# power_distribution_pcb.net
KiCad netlist of a schematic drawn in EAGLE
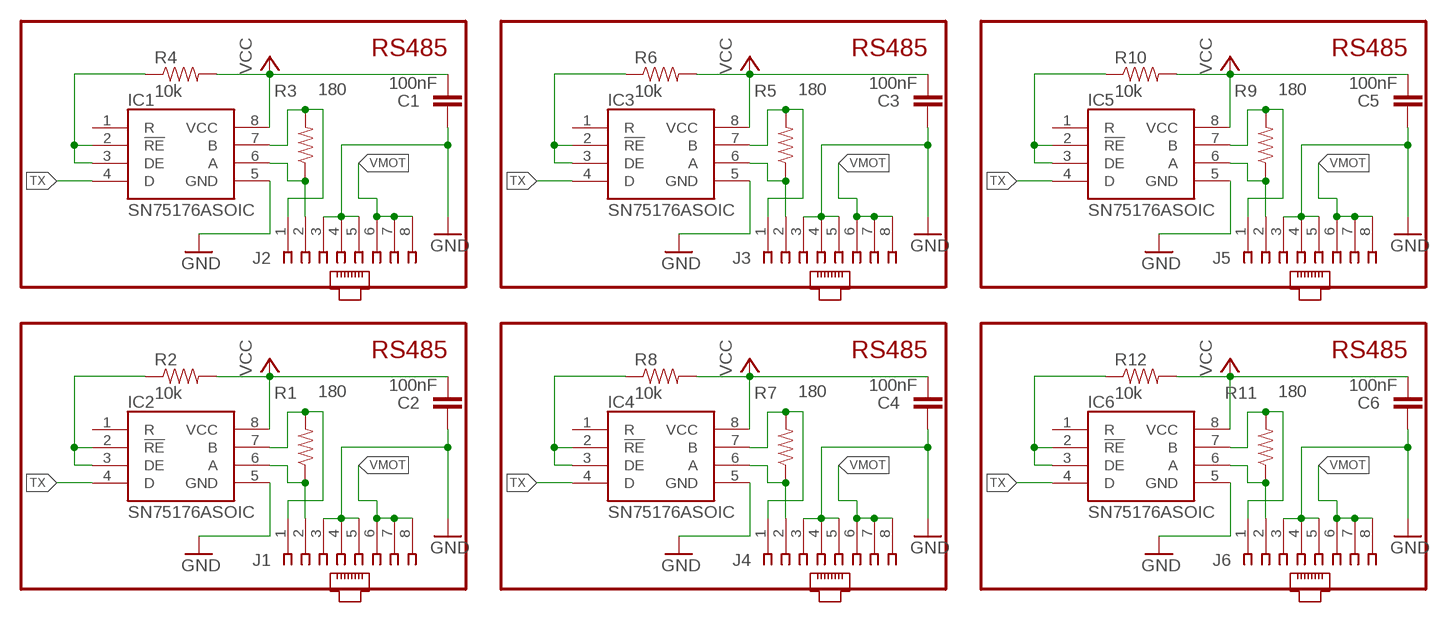
[diagram p0: schematic, sheet 1]

(export (version "E")
  (design (tool "Eeschema 10.0.6"))
  (components
    (comp (ref "C1")
      (value "100nF")
      (footprint "eagle-import:0805")
      (libsource (lib "eagle-import") (part "CAP0805"))
    )
    (comp (ref "C2")
      (value "100nF")
      (footprint "eagle-import:0805")
      (libsource (lib "eagle-import") (part "CAP0805"))
    )
    (comp (ref "C3")
      (value "100nF")
      (footprint "eagle-import:0805")
      (libsource (lib "eagle-import") (part "CAP0805"))
    )
    (comp (ref "C4")
      (value "100nF")
      (footprint "eagle-import:0805")
      (libsource (lib "eagle-import") (part "CAP0805"))
    )
    (comp (ref "C5")
      (value "100nF")
      (footprint "eagle-import:0805")
      (libsource (lib "eagle-import") (part "CAP0805"))
    )
    (comp (ref "C6")
      (value "100nF")
      (footprint "eagle-import:0805")
      (libsource (lib "eagle-import") (part "CAP0805"))
    )
    (comp (ref "IC1")
      (value "SN75176ASOIC")
      (footprint "eagle-import:SO08")
      (libsource (lib "eagle-import") (part "SN75176ASOIC"))
    )
    (comp (ref "IC2")
      (value "SN75176ASOIC")
      (footprint "eagle-import:SO08")
      (libsource (lib "eagle-import") (part "SN75176ASOIC"))
    )
    (comp (ref "IC3")
      (value "SN75176ASOIC")
      (footprint "eagle-import:SO08")
      (libsource (lib "eagle-import") (part "SN75176ASOIC"))
    )
    (comp (ref "IC4")
      (value "SN75176ASOIC")
      (footprint "eagle-import:SO08")
      (libsource (lib "eagle-import") (part "SN75176ASOIC"))
    )
    (comp (ref "IC5")
      (value "SN75176ASOIC")
      (footprint "eagle-import:SO08")
      (libsource (lib "eagle-import") (part "SN75176ASOIC"))
    )
    (comp (ref "IC6")
      (value "SN75176ASOIC")
      (footprint "eagle-import:SO08")
      (libsource (lib "eagle-import") (part "SN75176ASOIC"))
    )
    (comp (ref "J1")
      (value "520426-4")
      (footprint "eagle-import:520426-4")
      (libsource (lib "eagle-import") (part "520426-4"))
    )
    (comp (ref "J2")
      (value "520426-4")
      (footprint "eagle-import:520426-4")
      (libsource (lib "eagle-import") (part "520426-4"))
    )
    (comp (ref "J3")
      (value "520426-4")
      (footprint "eagle-import:520426-4")
      (libsource (lib "eagle-import") (part "520426-4"))
    )
    (comp (ref "J4")
      (value "520426-4")
      (footprint "eagle-import:520426-4")
      (libsource (lib "eagle-import") (part "520426-4"))
    )
    (comp (ref "J5")
      (value "520426-4")
      (footprint "eagle-import:520426-4")
      (libsource (lib "eagle-import") (part "520426-4"))
    )
    (comp (ref "J6")
      (value "520426-4")
      (footprint "eagle-import:520426-4")
      (libsource (lib "eagle-import") (part "520426-4"))
    )
    (comp (ref "R1")
      (value "180")
      (footprint "eagle-import:0805")
      (libsource (lib "eagle-import") (part "RESISTOR"))
    )
    (comp (ref "R2")
      (value "10k")
      (footprint "eagle-import:0805")
      (libsource (lib "eagle-import") (part "RESISTOR"))
    )
    (comp (ref "R3")
      (value "180")
      (footprint "eagle-import:0805")
      (libsource (lib "eagle-import") (part "RESISTOR"))
    )
    (comp (ref "R4")
      (value "10k")
      (footprint "eagle-import:0805")
      (libsource (lib "eagle-import") (part "RESISTOR"))
    )
    (comp (ref "R5")
      (value "180")
      (footprint "eagle-import:0805")
      (libsource (lib "eagle-import") (part "RESISTOR"))
    )
    (comp (ref "R6")
      (value "10k")
      (footprint "eagle-import:0805")
      (libsource (lib "eagle-import") (part "RESISTOR"))
    )
    (comp (ref "R7")
      (value "180")
      (footprint "eagle-import:0805")
      (libsource (lib "eagle-import") (part "RESISTOR"))
    )
    (comp (ref "R8")
      (value "10k")
      (footprint "eagle-import:0805")
      (libsource (lib "eagle-import") (part "RESISTOR"))
    )
    (comp (ref "R9")
      (value "180")
      (footprint "eagle-import:0805")
      (libsource (lib "eagle-import") (part "RESISTOR"))
    )
    (comp (ref "R10")
      (value "10k")
      (footprint "eagle-import:0805")
      (libsource (lib "eagle-import") (part "RESISTOR"))
    )
    (comp (ref "R11")
      (value "180")
      (footprint "eagle-import:0805")
      (libsource (lib "eagle-import") (part "RESISTOR"))
    )
    (comp (ref "R12")
      (value "10k")
      (footprint "eagle-import:0805")
      (libsource (lib "eagle-import") (part "RESISTOR"))
    )
  )
  (nets
    (net (code "1") (name "GND") (class "Default")
      (node (ref "C1") (pin "1") (pinfunction "1_1") (pintype "passive"))
      (node (ref "C2") (pin "1") (pinfunction "1_1") (pintype "passive"))
      (node (ref "C3") (pin "1") (pinfunction "1_1") (pintype "passive"))
      (node (ref "C4") (pin "1") (pinfunction "1_1") (pintype "passive"))
      (node (ref "C5") (pin "1") (pinfunction "1_1") (pintype "passive"))
      (node (ref "C6") (pin "1") (pinfunction "1_1") (pintype "passive"))
      (node (ref "IC1") (pin "5") (pinfunction "GND_5") (pintype "bidirectional"))
      (node (ref "IC2") (pin "5") (pinfunction "GND_5") (pintype "bidirectional"))
      (node (ref "IC3") (pin "5") (pinfunction "GND_5") (pintype "bidirectional"))
      (node (ref "IC4") (pin "5") (pinfunction "GND_5") (pintype "bidirectional"))
      (node (ref "IC5") (pin "5") (pinfunction "GND_5") (pintype "bidirectional"))
      (node (ref "IC6") (pin "5") (pinfunction "GND_5") (pintype "bidirectional"))
      (node (ref "J1") (pin "3") (pinfunction "3_3") (pintype "passive"))
      (node (ref "J1") (pin "4") (pinfunction "4_4") (pintype "passive"))
      (node (ref "J1") (pin "5") (pinfunction "5_5") (pintype "passive"))
      (node (ref "J2") (pin "3") (pinfunction "3_3") (pintype "passive"))
      (node (ref "J2") (pin "4") (pinfunction "4_4") (pintype "passive"))
      (node (ref "J2") (pin "5") (pinfunction "5_5") (pintype "passive"))
      (node (ref "J3") (pin "3") (pinfunction "3_3") (pintype "passive"))
      (node (ref "J3") (pin "4") (pinfunction "4_4") (pintype "passive"))
      (node (ref "J3") (pin "5") (pinfunction "5_5") (pintype "passive"))
      (node (ref "J4") (pin "3") (pinfunction "3_3") (pintype "passive"))
      (node (ref "J4") (pin "4") (pinfunction "4_4") (pintype "passive"))
      (node (ref "J4") (pin "5") (pinfunction "5_5") (pintype "passive"))
      (node (ref "J5") (pin "3") (pinfunction "3_3") (pintype "passive"))
      (node (ref "J5") (pin "4") (pinfunction "4_4") (pintype "passive"))
      (node (ref "J5") (pin "5") (pinfunction "5_5") (pintype "passive"))
      (node (ref "J6") (pin "3") (pinfunction "3_3") (pintype "passive"))
      (node (ref "J6") (pin "4") (pinfunction "4_4") (pintype "passive"))
      (node (ref "J6") (pin "5") (pinfunction "5_5") (pintype "passive"))
    )
    (net (code "2") (name "Net-(IC1-A)") (class "Default")
      (node (ref "IC1") (pin "6") (pinfunction "A_6") (pintype "bidirectional"))
      (node (ref "J2") (pin "2") (pinfunction "2_2") (pintype "passive"))
      (node (ref "R3") (pin "1") (pinfunction "1_1") (pintype "passive"))
    )
    (net (code "3") (name "Net-(IC1-B)") (class "Default")
      (node (ref "IC1") (pin "7") (pinfunction "B_7") (pintype "bidirectional"))
      (node (ref "J2") (pin "1") (pinfunction "1_1") (pintype "passive"))
      (node (ref "R3") (pin "2") (pinfunction "2_2") (pintype "passive"))
    )
    (net (code "4") (name "Net-(IC1-DE)") (class "Default")
      (node (ref "IC1") (pin "2") (pinfunction "~{RE}_2") (pintype "bidirectional"))
      (node (ref "IC1") (pin "3") (pinfunction "DE_3") (pintype "bidirectional"))
      (node (ref "R4") (pin "1") (pinfunction "1_1") (pintype "passive"))
    )
    (net (code "5") (name "Net-(IC2-A)") (class "Default")
      (node (ref "IC2") (pin "6") (pinfunction "A_6") (pintype "bidirectional"))
      (node (ref "J1") (pin "2") (pinfunction "2_2") (pintype "passive"))
      (node (ref "R1") (pin "1") (pinfunction "1_1") (pintype "passive"))
    )
    (net (code "6") (name "Net-(IC2-B)") (class "Default")
      (node (ref "IC2") (pin "7") (pinfunction "B_7") (pintype "bidirectional"))
      (node (ref "J1") (pin "1") (pinfunction "1_1") (pintype "passive"))
      (node (ref "R1") (pin "2") (pinfunction "2_2") (pintype "passive"))
    )
    (net (code "7") (name "Net-(IC2-DE)") (class "Default")
      (node (ref "IC2") (pin "2") (pinfunction "~{RE}_2") (pintype "bidirectional"))
      (node (ref "IC2") (pin "3") (pinfunction "DE_3") (pintype "bidirectional"))
      (node (ref "R2") (pin "1") (pinfunction "1_1") (pintype "passive"))
    )
    (net (code "8") (name "Net-(IC3-A)") (class "Default")
      (node (ref "IC3") (pin "6") (pinfunction "A_6") (pintype "bidirectional"))
      (node (ref "J3") (pin "2") (pinfunction "2_2") (pintype "passive"))
      (node (ref "R5") (pin "1") (pinfunction "1_1") (pintype "passive"))
    )
    (net (code "9") (name "Net-(IC3-B)") (class "Default")
      (node (ref "IC3") (pin "7") (pinfunction "B_7") (pintype "bidirectional"))
      (node (ref "J3") (pin "1") (pinfunction "1_1") (pintype "passive"))
      (node (ref "R5") (pin "2") (pinfunction "2_2") (pintype "passive"))
    )
    (net (code "10") (name "Net-(IC3-DE)") (class "Default")
      (node (ref "IC3") (pin "2") (pinfunction "~{RE}_2") (pintype "bidirectional"))
      (node (ref "IC3") (pin "3") (pinfunction "DE_3") (pintype "bidirectional"))
      (node (ref "R6") (pin "1") (pinfunction "1_1") (pintype "passive"))
    )
    (net (code "11") (name "Net-(IC4-A)") (class "Default")
      (node (ref "IC4") (pin "6") (pinfunction "A_6") (pintype "bidirectional"))
      (node (ref "J4") (pin "2") (pinfunction "2_2") (pintype "passive"))
      (node (ref "R7") (pin "1") (pinfunction "1_1") (pintype "passive"))
    )
    (net (code "12") (name "Net-(IC4-B)") (class "Default")
      (node (ref "IC4") (pin "7") (pinfunction "B_7") (pintype "bidirectional"))
      (node (ref "J4") (pin "1") (pinfunction "1_1") (pintype "passive"))
      (node (ref "R7") (pin "2") (pinfunction "2_2") (pintype "passive"))
    )
    (net (code "13") (name "Net-(IC4-DE)") (class "Default")
      (node (ref "IC4") (pin "2") (pinfunction "~{RE}_2") (pintype "bidirectional"))
      (node (ref "IC4") (pin "3") (pinfunction "DE_3") (pintype "bidirectional"))
      (node (ref "R8") (pin "1") (pinfunction "1_1") (pintype "passive"))
    )
    (net (code "14") (name "Net-(IC5-A)") (class "Default")
      (node (ref "IC5") (pin "6") (pinfunction "A_6") (pintype "bidirectional"))
      (node (ref "J5") (pin "2") (pinfunction "2_2") (pintype "passive"))
      (node (ref "R9") (pin "1") (pinfunction "1_1") (pintype "passive"))
    )
    (net (code "15") (name "Net-(IC5-B)") (class "Default")
      (node (ref "IC5") (pin "7") (pinfunction "B_7") (pintype "bidirectional"))
      (node (ref "J5") (pin "1") (pinfunction "1_1") (pintype "passive"))
      (node (ref "R9") (pin "2") (pinfunction "2_2") (pintype "passive"))
    )
    (net (code "16") (name "Net-(IC5-DE)") (class "Default")
      (node (ref "IC5") (pin "2") (pinfunction "~{RE}_2") (pintype "bidirectional"))
      (node (ref "IC5") (pin "3") (pinfunction "DE_3") (pintype "bidirectional"))
      (node (ref "R10") (pin "1") (pinfunction "1_1") (pintype "passive"))
    )
    (net (code "17") (name "Net-(IC6-A)") (class "Default")
      (node (ref "IC6") (pin "6") (pinfunction "A_6") (pintype "bidirectional"))
      (node (ref "J6") (pin "2") (pinfunction "2_2") (pintype "passive"))
      (node (ref "R11") (pin "1") (pinfunction "1_1") (pintype "passive"))
    )
    (net (code "18") (name "Net-(IC6-B)") (class "Default")
      (node (ref "IC6") (pin "7") (pinfunction "B_7") (pintype "bidirectional"))
      (node (ref "J6") (pin "1") (pinfunction "1_1") (pintype "passive"))
      (node (ref "R11") (pin "2") (pinfunction "2_2") (pintype "passive"))
    )
    (net (code "19") (name "Net-(IC6-DE)") (class "Default")
      (node (ref "IC6") (pin "2") (pinfunction "~{RE}_2") (pintype "bidirectional"))
      (node (ref "IC6") (pin "3") (pinfunction "DE_3") (pintype "bidirectional"))
      (node (ref "R12") (pin "1") (pinfunction "1_1") (pintype "passive"))
    )
    (net (code "20") (name "TX") (class "Default")
      (node (ref "IC1") (pin "4") (pinfunction "D_4") (pintype "bidirectional"))
      (node (ref "IC2") (pin "4") (pinfunction "D_4") (pintype "bidirectional"))
      (node (ref "IC3") (pin "4") (pinfunction "D_4") (pintype "bidirectional"))
      (node (ref "IC4") (pin "4") (pinfunction "D_4") (pintype "bidirectional"))
      (node (ref "IC5") (pin "4") (pinfunction "D_4") (pintype "bidirectional"))
      (node (ref "IC6") (pin "4") (pinfunction "D_4") (pintype "bidirectional"))
    )
    (net (code "21") (name "VCC") (class "Default")
      (node (ref "C1") (pin "2") (pinfunction "2_2") (pintype "passive"))
      (node (ref "C2") (pin "2") (pinfunction "2_2") (pintype "passive"))
      (node (ref "C3") (pin "2") (pinfunction "2_2") (pintype "passive"))
      (node (ref "C4") (pin "2") (pinfunction "2_2") (pintype "passive"))
      (node (ref "C5") (pin "2") (pinfunction "2_2") (pintype "passive"))
      (node (ref "C6") (pin "2") (pinfunction "2_2") (pintype "passive"))
      (node (ref "IC1") (pin "8") (pinfunction "VCC_8") (pintype "bidirectional"))
      (node (ref "IC2") (pin "8") (pinfunction "VCC_8") (pintype "bidirectional"))
      (node (ref "IC3") (pin "8") (pinfunction "VCC_8") (pintype "bidirectional"))
      (node (ref "IC4") (pin "8") (pinfunction "VCC_8") (pintype "bidirectional"))
      (node (ref "IC5") (pin "8") (pinfunction "VCC_8") (pintype "bidirectional"))
      (node (ref "IC6") (pin "8") (pinfunction "VCC_8") (pintype "bidirectional"))
      (node (ref "R10") (pin "2") (pinfunction "2_2") (pintype "passive"))
      (node (ref "R12") (pin "2") (pinfunction "2_2") (pintype "passive"))
      (node (ref "R2") (pin "2") (pinfunction "2_2") (pintype "passive"))
      (node (ref "R4") (pin "2") (pinfunction "2_2") (pintype "passive"))
      (node (ref "R6") (pin "2") (pinfunction "2_2") (pintype "passive"))
      (node (ref "R8") (pin "2") (pinfunction "2_2") (pintype "passive"))
    )
    (net (code "22") (name "VMOT") (class "Default")
      (node (ref "J1") (pin "6") (pinfunction "6_6") (pintype "passive"))
      (node (ref "J1") (pin "7") (pinfunction "7_7") (pintype "passive"))
      (node (ref "J1") (pin "8") (pinfunction "8_8") (pintype "passive"))
      (node (ref "J2") (pin "6") (pinfunction "6_6") (pintype "passive"))
      (node (ref "J2") (pin "7") (pinfunction "7_7") (pintype "passive"))
      (node (ref "J2") (pin "8") (pinfunction "8_8") (pintype "passive"))
      (node (ref "J3") (pin "6") (pinfunction "6_6") (pintype "passive"))
      (node (ref "J3") (pin "7") (pinfunction "7_7") (pintype "passive"))
      (node (ref "J3") (pin "8") (pinfunction "8_8") (pintype "passive"))
      (node (ref "J4") (pin "6") (pinfunction "6_6") (pintype "passive"))
      (node (ref "J4") (pin "7") (pinfunction "7_7") (pintype "passive"))
      (node (ref "J4") (pin "8") (pinfunction "8_8") (pintype "passive"))
      (node (ref "J5") (pin "6") (pinfunction "6_6") (pintype "passive"))
      (node (ref "J5") (pin "7") (pinfunction "7_7") (pintype "passive"))
      (node (ref "J5") (pin "8") (pinfunction "8_8") (pintype "passive"))
      (node (ref "J6") (pin "6") (pinfunction "6_6") (pintype "passive"))
      (node (ref "J6") (pin "7") (pinfunction "7_7") (pintype "passive"))
      (node (ref "J6") (pin "8") (pinfunction "8_8") (pintype "passive"))
    )
    (net (code "23") (name "unconnected-(IC1-R-Pad1)") (class "Default")
      (node (ref "IC1") (pin "1") (pinfunction "R_1") (pintype "bidirectional"))
    )
    (net (code "24") (name "unconnected-(IC2-R-Pad1)") (class "Default")
      (node (ref "IC2") (pin "1") (pinfunction "R_1") (pintype "bidirectional"))
    )
    (net (code "25") (name "unconnected-(IC3-R-Pad1)") (class "Default")
      (node (ref "IC3") (pin "1") (pinfunction "R_1") (pintype "bidirectional"))
    )
    (net (code "26") (name "unconnected-(IC4-R-Pad1)") (class "Default")
      (node (ref "IC4") (pin "1") (pinfunction "R_1") (pintype "bidirectional"))
    )
    (net (code "27") (name "unconnected-(IC5-R-Pad1)") (class "Default")
      (node (ref "IC5") (pin "1") (pinfunction "R_1") (pintype "bidirectional"))
    )
    (net (code "28") (name "unconnected-(IC6-R-Pad1)") (class "Default")
      (node (ref "IC6") (pin "1") (pinfunction "R_1") (pintype "bidirectional"))
    )
  )
)
